# hand.net
KiCad netlist of a schematic drawn in EasyEDA
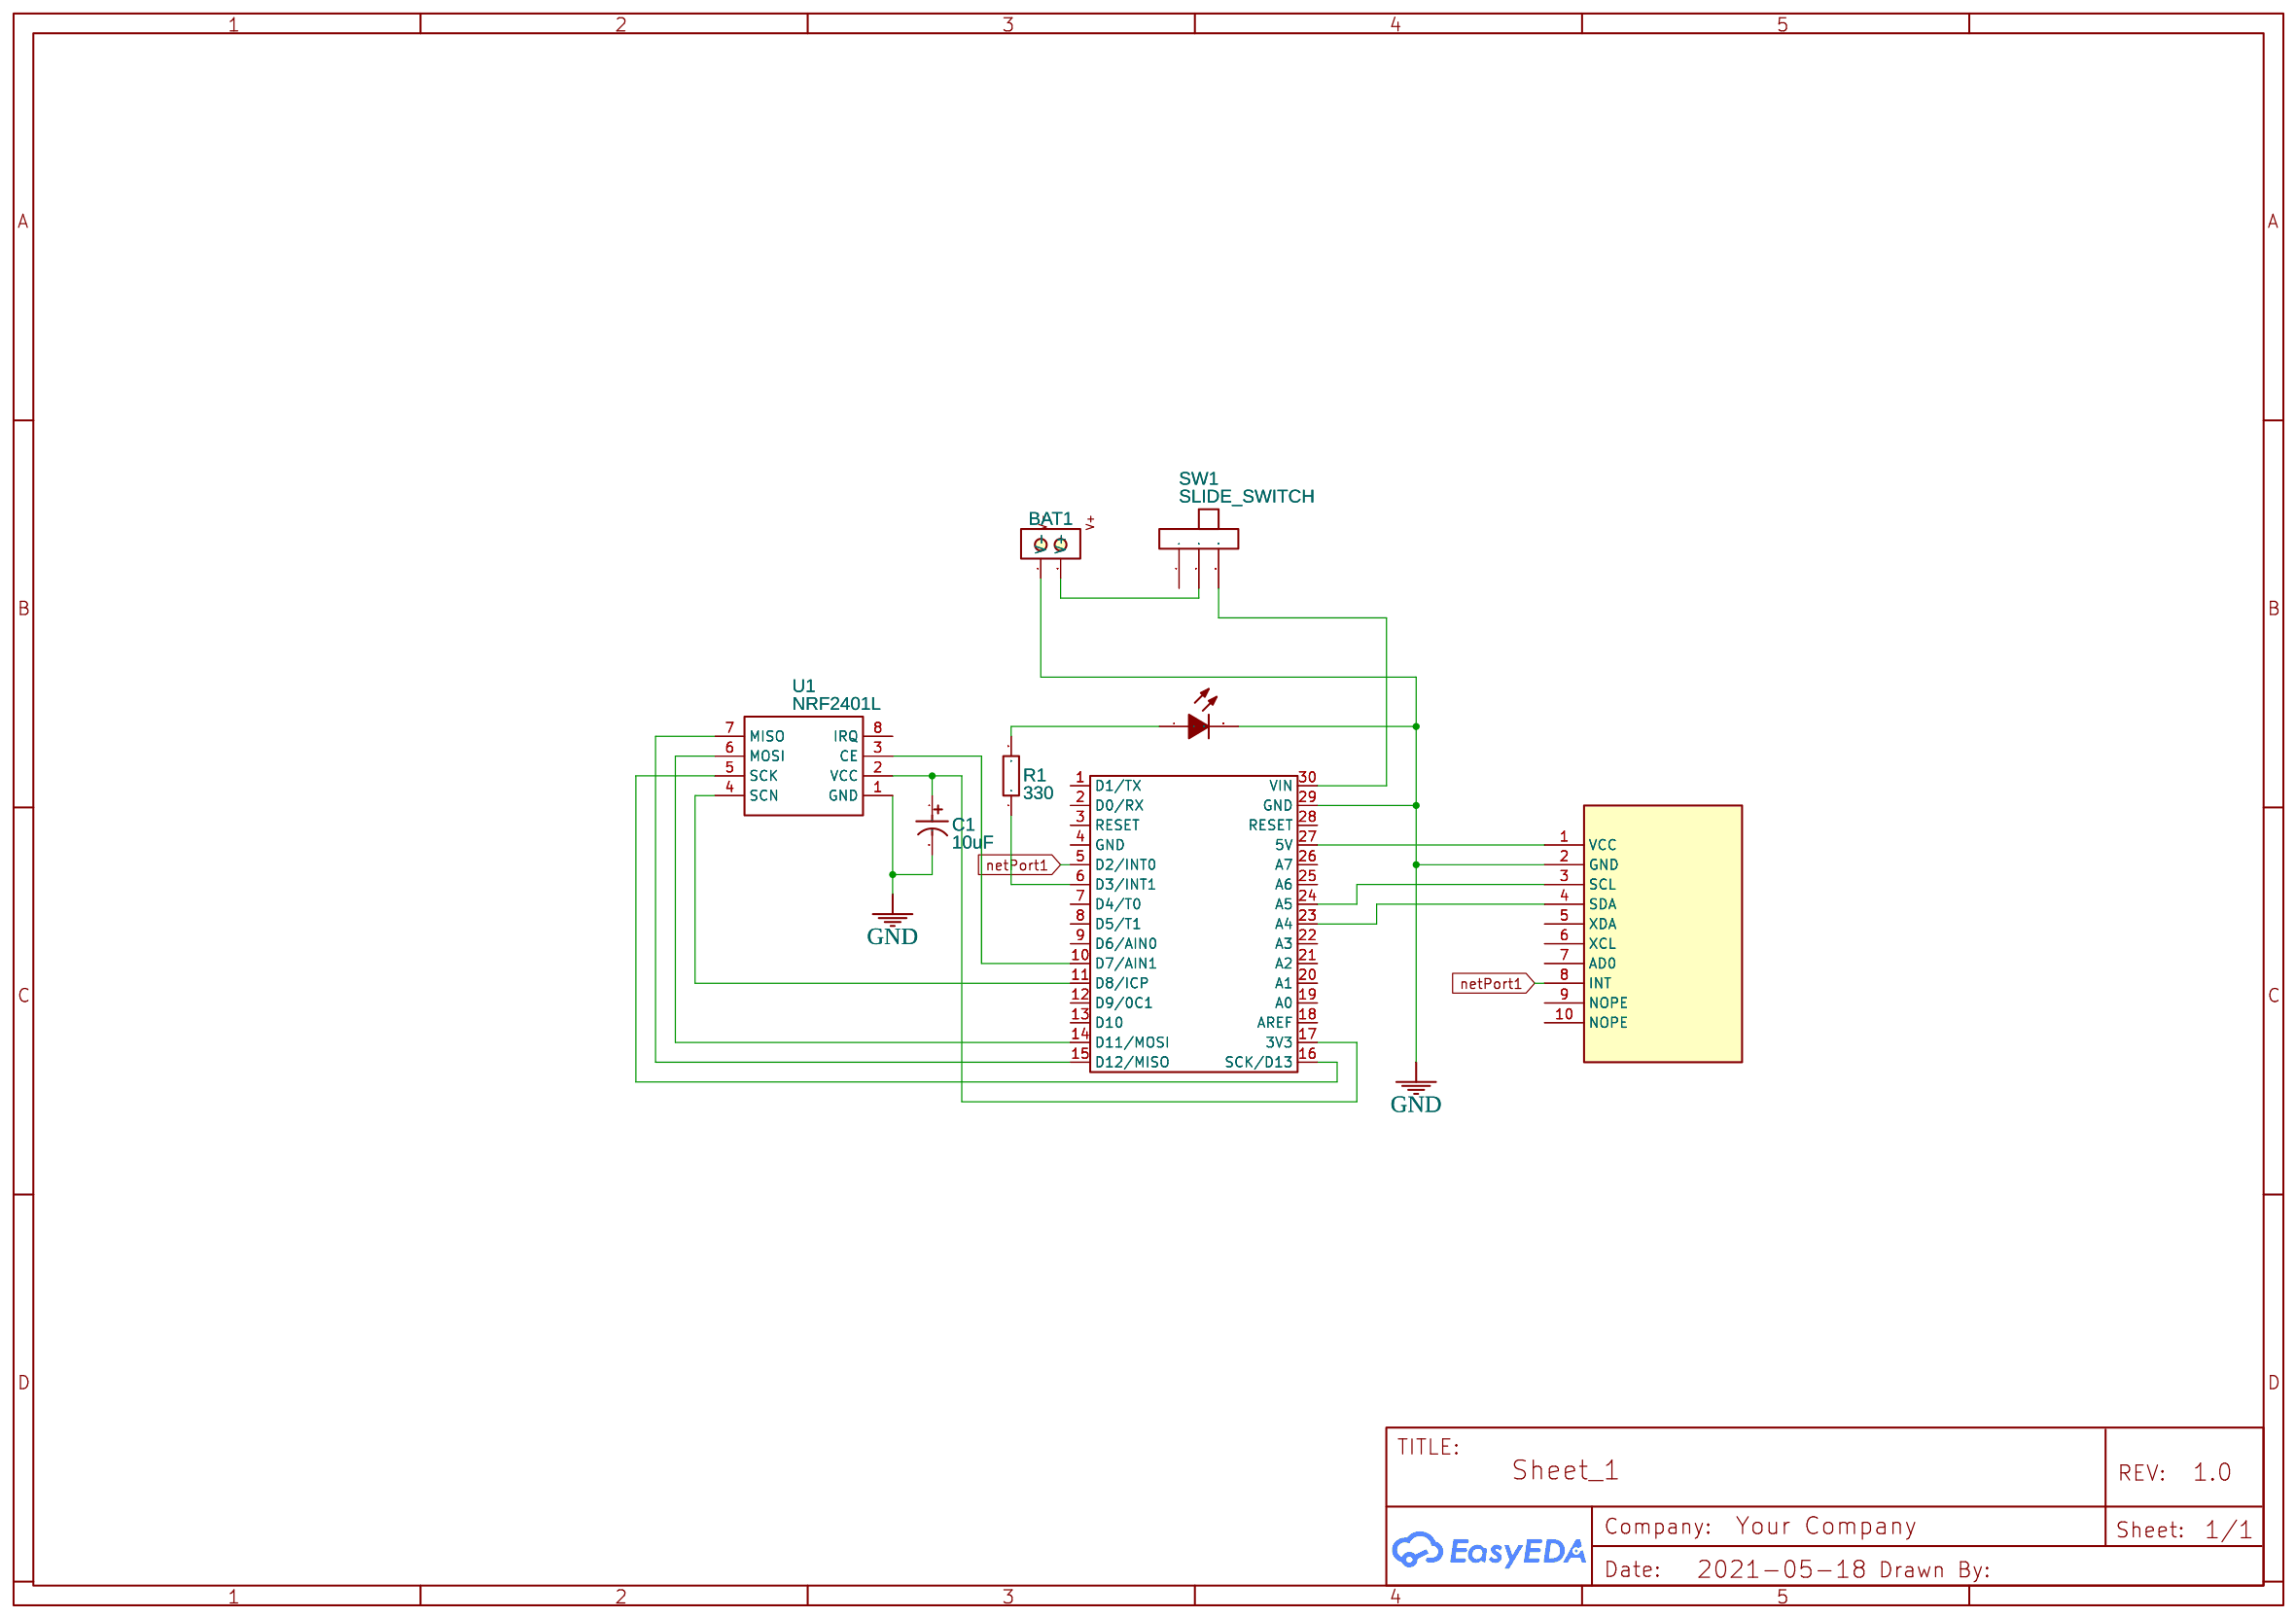
[diagram p0: schematic sheet]

(export (version "E")
  (design (tool "Eeschema 10.0.6"))
  (components
    (comp (ref "BAT1")
      (value "9V Battery cable connector")
      (libsource (lib "") (part "9V Battery cable connector"))
    )
    (comp (ref "C1")
      (value "10uF")
      (fields
        (field (name "BOM_Manufacturer Part") "electrolytic capacitor10UF50V")
        (field (name "BOM_Supplier Part") "C32856")
      )
      (libsource (lib "") (part "electrolytic capacitor10UF50V"))
    )
    (comp (ref "J1") (value "Arduino_Nano_Header") (libsource (lib "") (part "Arduino_Nano_Header")))
    (comp (ref "LED1")
      (value "φ3 Red")
      (fields (field (name "BOM_Supplier Part") "C39928"))
      (libsource (lib "") (part "φ3 Red"))
    )
    (comp (ref "P1") (value "MPU6050") (libsource (lib "") (part "MPU6050")))
    (comp (ref "R1")
      (value "330")
      (fields
        (field (name "BOM_Manufacturer Part") "MF1/8W ±1% 330Ω OTB5")
        (field (name "BOM_Supplier Part") "C337130")
      )
      (libsource (lib "") (part "MF1/8W ±1% 330Ω OTB5"))
    )
    (comp (ref "SW1")
      (value "SLIDE_SWITCH")
      (fields
        (field (name "BOM_Manufacturer Part") "slide switch")
        (field (name "BOM_Supplier Part") "401-1999-1-ND")
      )
      (libsource (lib "") (part "SLIDE_SWITCH"))
    )
    (comp (ref "U1")
      (value "NRF2401L")
      (fields (field (name "BOM_Manufacturer Part") "nrf2401l"))
      (libsource (lib "") (part "NRF2401L"))
    )
  )
  (nets
    (net (code "1") (name "GND") (class "Default")
      (node (ref "BAT1") (pin "1") (pinfunction "V-_1") (pintype "unspecified"))
      (node (ref "C1") (pin "2") (pinfunction "-_2") (pintype "input"))
      (node (ref "J1") (pin "29") (pinfunction "GND_29") (pintype "unspecified"))
      (node (ref "LED1") (pin "2") (pinfunction "C_2") (pintype "input"))
      (node (ref "P1") (pin "2") (pinfunction "GND_2") (pintype "unspecified"))
      (node (ref "U1") (pin "1") (pinfunction "GND_1") (pintype "unspecified"))
    )
    (net (code "2") (name "Net-(BAT1-V+)") (class "Default")
      (node (ref "BAT1") (pin "2") (pinfunction "V+_2") (pintype "unspecified"))
      (node (ref "SW1") (pin "2") (pinfunction "2_2") (pintype "unspecified"))
    )
    (net (code "3") (name "Net-(C1-+)") (class "Default")
      (node (ref "C1") (pin "1") (pinfunction "+_1") (pintype "input"))
      (node (ref "J1") (pin "17") (pinfunction "3V3_17") (pintype "unspecified"))
      (node (ref "U1") (pin "2") (pinfunction "VCC_2") (pintype "unspecified"))
    )
    (net (code "4") (name "Net-(J1-5V)") (class "Default")
      (node (ref "J1") (pin "27") (pinfunction "5V_27") (pintype "unspecified"))
      (node (ref "P1") (pin "1") (pinfunction "VCC_1") (pintype "unspecified"))
    )
    (net (code "5") (name "Net-(J1-A4)") (class "Default")
      (node (ref "J1") (pin "23") (pinfunction "A4_23") (pintype "unspecified"))
      (node (ref "P1") (pin "4") (pinfunction "SDA_4") (pintype "unspecified"))
    )
    (net (code "6") (name "Net-(J1-A5)") (class "Default")
      (node (ref "J1") (pin "24") (pinfunction "A5_24") (pintype "unspecified"))
      (node (ref "P1") (pin "3") (pinfunction "SCL_3") (pintype "unspecified"))
    )
    (net (code "7") (name "Net-(J1-D3{slash}INT1)") (class "Default")
      (node (ref "J1") (pin "6") (pinfunction "D3/INT1_6") (pintype "unspecified"))
      (node (ref "R1") (pin "1") (pinfunction "1_1") (pintype "unspecified"))
    )
    (net (code "8") (name "Net-(J1-D7{slash}AIN1)") (class "Default")
      (node (ref "J1") (pin "10") (pinfunction "D7/AIN1_10") (pintype "unspecified"))
      (node (ref "U1") (pin "3") (pinfunction "CE_3") (pintype "unspecified"))
    )
    (net (code "9") (name "Net-(J1-D8{slash}ICP)") (class "Default")
      (node (ref "J1") (pin "11") (pinfunction "D8/ICP_11") (pintype "unspecified"))
      (node (ref "U1") (pin "4") (pinfunction "SCN_4") (pintype "unspecified"))
    )
    (net (code "10") (name "Net-(J1-D11{slash}MOSI)") (class "Default")
      (node (ref "J1") (pin "14") (pinfunction "D11/MOSI_14") (pintype "unspecified"))
      (node (ref "U1") (pin "6") (pinfunction "MOSI_6") (pintype "unspecified"))
    )
    (net (code "11") (name "Net-(J1-D12{slash}MISO)") (class "Default")
      (node (ref "J1") (pin "15") (pinfunction "D12/MISO_15") (pintype "unspecified"))
      (node (ref "U1") (pin "7") (pinfunction "MISO_7") (pintype "unspecified"))
    )
    (net (code "12") (name "Net-(J1-SCK{slash}D13)") (class "Default")
      (node (ref "J1") (pin "16") (pinfunction "SCK/D13_16") (pintype "unspecified"))
      (node (ref "U1") (pin "5") (pinfunction "SCK_5") (pintype "unspecified"))
    )
    (net (code "13") (name "Net-(J1-VIN)") (class "Default")
      (node (ref "J1") (pin "30") (pinfunction "VIN_30") (pintype "unspecified"))
      (node (ref "SW1") (pin "3") (pinfunction "3_3") (pintype "unspecified"))
    )
    (net (code "14") (name "Net-(LED1-A)") (class "Default")
      (node (ref "LED1") (pin "1") (pinfunction "A_1") (pintype "input"))
      (node (ref "R1") (pin "2") (pinfunction "2_2") (pintype "unspecified"))
    )
    (net (code "15") (name "netPort1") (class "Default")
      (node (ref "J1") (pin "5") (pinfunction "D2/INT0_5") (pintype "unspecified"))
      (node (ref "P1") (pin "8") (pinfunction "INT_8") (pintype "unspecified"))
    )
    (net (code "16") (name "unconnected-(J1-A0-Pad19)") (class "Default")
      (node (ref "J1") (pin "19") (pinfunction "A0_19") (pintype "unspecified"))
    )
    (net (code "17") (name "unconnected-(J1-A1-Pad20)") (class "Default")
      (node (ref "J1") (pin "20") (pinfunction "A1_20") (pintype "unspecified"))
    )
    (net (code "18") (name "unconnected-(J1-A2-Pad21)") (class "Default")
      (node (ref "J1") (pin "21") (pinfunction "A2_21") (pintype "unspecified"))
    )
    (net (code "19") (name "unconnected-(J1-A3-Pad22)") (class "Default")
      (node (ref "J1") (pin "22") (pinfunction "A3_22") (pintype "unspecified"))
    )
    (net (code "20") (name "unconnected-(J1-A6-Pad25)") (class "Default")
      (node (ref "J1") (pin "25") (pinfunction "A6_25") (pintype "unspecified"))
    )
    (net (code "21") (name "unconnected-(J1-A7-Pad26)") (class "Default")
      (node (ref "J1") (pin "26") (pinfunction "A7_26") (pintype "unspecified"))
    )
    (net (code "22") (name "unconnected-(J1-AREF-Pad18)") (class "Default")
      (node (ref "J1") (pin "18") (pinfunction "AREF_18") (pintype "unspecified"))
    )
    (net (code "23") (name "unconnected-(J1-D0{slash}RX-Pad2)") (class "Default")
      (node (ref "J1") (pin "2") (pinfunction "D0/RX_2") (pintype "unspecified"))
    )
    (net (code "24") (name "unconnected-(J1-D1{slash}TX-Pad1)") (class "Default")
      (node (ref "J1") (pin "1") (pinfunction "D1/TX_1") (pintype "unspecified"))
    )
    (net (code "25") (name "unconnected-(J1-D4{slash}T0-Pad7)") (class "Default")
      (node (ref "J1") (pin "7") (pinfunction "D4/T0_7") (pintype "unspecified"))
    )
    (net (code "26") (name "unconnected-(J1-D5{slash}T1-Pad8)") (class "Default")
      (node (ref "J1") (pin "8") (pinfunction "D5/T1_8") (pintype "unspecified"))
    )
    (net (code "27") (name "unconnected-(J1-D6{slash}AIN0-Pad9)") (class "Default")
      (node (ref "J1") (pin "9") (pinfunction "D6/AIN0_9") (pintype "unspecified"))
    )
    (net (code "28") (name "unconnected-(J1-D9{slash}0C1-Pad12)") (class "Default")
      (node (ref "J1") (pin "12") (pinfunction "D9/0C1_12") (pintype "unspecified"))
    )
    (net (code "29") (name "unconnected-(J1-D10-Pad13)") (class "Default")
      (node (ref "J1") (pin "13") (pinfunction "D10_13") (pintype "unspecified"))
    )
    (net (code "30") (name "unconnected-(J1-GND-Pad4)") (class "Default")
      (node (ref "J1") (pin "4") (pinfunction "GND_4") (pintype "unspecified"))
    )
    (net (code "31") (name "unconnected-(J1-RESET-Pad3)") (class "Default")
      (node (ref "J1") (pin "3") (pinfunction "RESET_3") (pintype "unspecified"))
    )
    (net (code "32") (name "unconnected-(J1-RESET-Pad28)") (class "Default")
      (node (ref "J1") (pin "28") (pinfunction "RESET_28") (pintype "unspecified"))
    )
    (net (code "33") (name "unconnected-(P1-AD0-Pad7)") (class "Default")
      (node (ref "P1") (pin "7") (pinfunction "AD0_7") (pintype "unspecified"))
    )
    (net (code "34") (name "unconnected-(P1-NOPE-Pad9)") (class "Default")
      (node (ref "P1") (pin "9") (pinfunction "NOPE_9") (pintype "unspecified"))
    )
    (net (code "35") (name "unconnected-(P1-NOPE-Pad10)") (class "Default")
      (node (ref "P1") (pin "10") (pinfunction "NOPE_10") (pintype "unspecified"))
    )
    (net (code "36") (name "unconnected-(P1-XCL-Pad6)") (class "Default")
      (node (ref "P1") (pin "6") (pinfunction "XCL_6") (pintype "unspecified"))
    )
    (net (code "37") (name "unconnected-(P1-XDA-Pad5)") (class "Default")
      (node (ref "P1") (pin "5") (pinfunction "XDA_5") (pintype "unspecified"))
    )
    (net (code "38") (name "unconnected-(SW1-Pad1)") (class "Default")
      (node (ref "SW1") (pin "1") (pinfunction "1_1") (pintype "unspecified"))
    )
    (net (code "39") (name "unconnected-(U1-IRQ-Pad8)") (class "Default")
      (node (ref "U1") (pin "8") (pinfunction "IRQ_8") (pintype "unspecified"))
    )
  )
)
